# 307.net
KiCad netlist of a schematic drawn in EAGLE
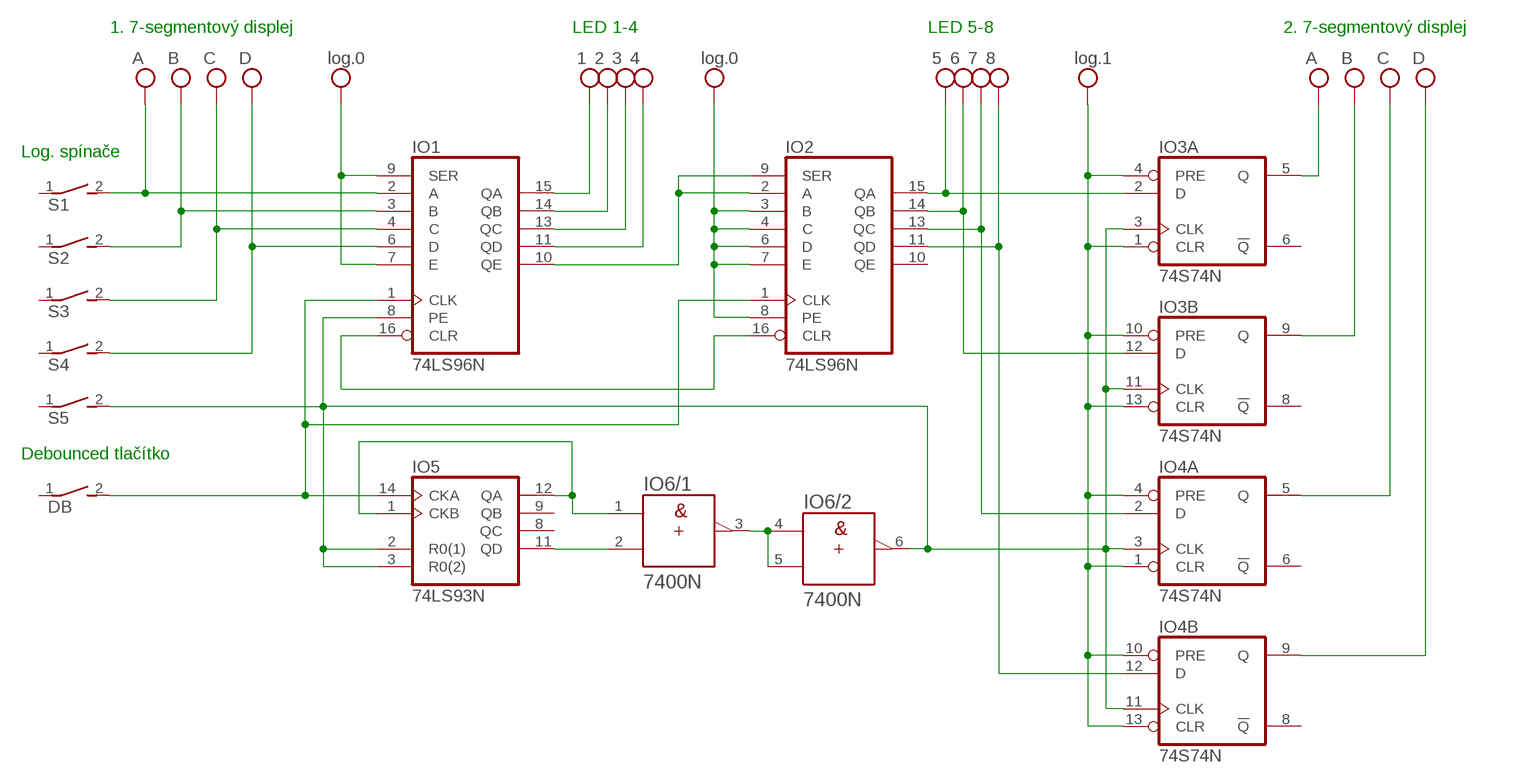
[diagram p0: schematic, sheet 1]

(export (version "E")
  (design (tool "Eeschema 10.0.6"))
  (components
    (comp (ref "DB")
      (value "DS01E")
      (footprint "eagle-import:DS-01")
      (libsource (lib "eagle-import") (part "DS01E"))
    )
    (comp (ref "IO1")
      (value "74LS96N")
      (footprint "eagle-import:DIL16")
      (libsource (lib "eagle-import") (part "7496NLS"))
    )
    (comp (ref "IO2")
      (value "74LS96N")
      (footprint "eagle-import:DIL16")
      (libsource (lib "eagle-import") (part "7496NLS"))
    )
    (comp (ref "IO3")
      (value "74S74N")
      (footprint "eagle-import:DIL14")
      (libsource (lib "eagle-import") (part "7474NS"))
    )
    (comp (ref "IO4")
      (value "74S74N")
      (footprint "eagle-import:DIL14")
      (libsource (lib "eagle-import") (part "7474NS"))
    )
    (comp (ref "IO5")
      (value "74LS93N")
      (footprint "eagle-import:DIL14")
      (libsource (lib "eagle-import") (part "7493NLS"))
    )
    (comp (ref "IO6")
      (value "7400N")
      (footprint "eagle-import:DIL14")
      (libsource (lib "eagle-import") (part "7400N"))
    )
    (comp (ref "S1")
      (value "DS01E")
      (footprint "eagle-import:DS-01")
      (libsource (lib "eagle-import") (part "DS01E"))
    )
    (comp (ref "S2")
      (value "DS01E")
      (footprint "eagle-import:DS-01")
      (libsource (lib "eagle-import") (part "DS01E"))
    )
    (comp (ref "S3")
      (value "DS01E")
      (footprint "eagle-import:DS-01")
      (libsource (lib "eagle-import") (part "DS01E"))
    )
    (comp (ref "S4")
      (value "DS01E")
      (footprint "eagle-import:DS-01")
      (libsource (lib "eagle-import") (part "DS01E"))
    )
    (comp (ref "S5")
      (value "DS01E")
      (footprint "eagle-import:DS-01")
      (libsource (lib "eagle-import") (part "DS01E"))
    )
  )
  (nets
    (net (code "1") (name "1") (class "Default")
      (node (ref "IO1") (pin "11") (pinfunction "QD_11") (pintype "output"))
      (node (ref "IO1") (pin "13") (pinfunction "QC_13") (pintype "output"))
      (node (ref "IO1") (pin "14") (pinfunction "QB_14") (pintype "output"))
      (node (ref "IO1") (pin "15") (pinfunction "QA_15") (pintype "output"))
      (node (ref "IO1") (pin "2") (pinfunction "A_2") (pintype "input"))
      (node (ref "IO1") (pin "3") (pinfunction "B_3") (pintype "input"))
      (node (ref "IO1") (pin "4") (pinfunction "C_4") (pintype "input"))
      (node (ref "IO1") (pin "6") (pinfunction "D_6") (pintype "input"))
      (node (ref "IO1") (pin "7") (pinfunction "E_7") (pintype "input"))
      (node (ref "IO1") (pin "9") (pinfunction "SER_9") (pintype "input"))
      (node (ref "IO2") (pin "11") (pinfunction "QD_11") (pintype "output"))
      (node (ref "IO2") (pin "13") (pinfunction "QC_13") (pintype "output"))
      (node (ref "IO2") (pin "14") (pinfunction "QB_14") (pintype "output"))
      (node (ref "IO2") (pin "15") (pinfunction "QA_15") (pintype "output"))
      (node (ref "IO2") (pin "3") (pinfunction "B_3") (pintype "input"))
      (node (ref "IO2") (pin "4") (pinfunction "C_4") (pintype "input"))
      (node (ref "IO2") (pin "6") (pinfunction "D_6") (pintype "input"))
      (node (ref "IO2") (pin "7") (pinfunction "E_7") (pintype "input"))
      (node (ref "IO2") (pin "8") (pinfunction "PE_8") (pintype "input"))
      (node (ref "IO3") (pin "1") (pinfunction "CLR_1") (pintype "input"))
      (node (ref "IO3") (pin "10") (pinfunction "PRE_10") (pintype "input"))
      (node (ref "IO3") (pin "12") (pinfunction "D_12") (pintype "input"))
      (node (ref "IO3") (pin "13") (pinfunction "CLR_13") (pintype "input"))
      (node (ref "IO3") (pin "2") (pinfunction "D_2") (pintype "input"))
      (node (ref "IO3") (pin "4") (pinfunction "PRE_4") (pintype "input"))
      (node (ref "IO3") (pin "5") (pinfunction "Q_5") (pintype "output"))
      (node (ref "IO3") (pin "9") (pinfunction "Q_9") (pintype "output"))
      (node (ref "IO4") (pin "1") (pinfunction "CLR_1") (pintype "input"))
      (node (ref "IO4") (pin "10") (pinfunction "PRE_10") (pintype "input"))
      (node (ref "IO4") (pin "12") (pinfunction "D_12") (pintype "input"))
      (node (ref "IO4") (pin "13") (pinfunction "CLR_13") (pintype "input"))
      (node (ref "IO4") (pin "2") (pinfunction "D_2") (pintype "input"))
      (node (ref "IO4") (pin "4") (pinfunction "PRE_4") (pintype "input"))
      (node (ref "IO4") (pin "5") (pinfunction "Q_5") (pintype "output"))
      (node (ref "IO4") (pin "9") (pinfunction "Q_9") (pintype "output"))
      (node (ref "S1") (pin "2") (pinfunction "2_2") (pintype "passive"))
      (node (ref "S2") (pin "2") (pinfunction "2_2") (pintype "passive"))
      (node (ref "S3") (pin "2") (pinfunction "2_2") (pintype "passive"))
      (node (ref "S4") (pin "2") (pinfunction "2_2") (pintype "passive"))
    )
    (net (code "2") (name "Net-(IO1A-CLK)") (class "Default")
      (node (ref "DB") (pin "2") (pinfunction "2_2") (pintype "passive"))
      (node (ref "IO1") (pin "1") (pinfunction "CLK_1") (pintype "input"))
      (node (ref "IO2") (pin "1") (pinfunction "CLK_1") (pintype "input"))
      (node (ref "IO5") (pin "14") (pinfunction "CKA_14") (pintype "input"))
    )
    (net (code "3") (name "Net-(IO1A-CLR)") (class "Default")
      (node (ref "IO1") (pin "16") (pinfunction "CLR_16") (pintype "input"))
      (node (ref "IO2") (pin "16") (pinfunction "CLR_16") (pintype "input"))
    )
    (net (code "4") (name "Net-(IO1A-PE)") (class "Default")
      (node (ref "IO1") (pin "8") (pinfunction "PE_8") (pintype "input"))
      (node (ref "IO3") (pin "11") (pinfunction "CLK_11") (pintype "input"))
      (node (ref "IO3") (pin "3") (pinfunction "CLK_3") (pintype "input"))
      (node (ref "IO4") (pin "11") (pinfunction "CLK_11") (pintype "input"))
      (node (ref "IO4") (pin "3") (pinfunction "CLK_3") (pintype "input"))
      (node (ref "IO5") (pin "2") (pinfunction "R0(1)_2") (pintype "input"))
      (node (ref "IO5") (pin "3") (pinfunction "R0(2)_3") (pintype "input"))
      (node (ref "IO6") (pin "6") (pinfunction "Y_6") (pintype "output"))
      (node (ref "S5") (pin "2") (pinfunction "2_2") (pintype "passive"))
    )
    (net (code "5") (name "Net-(IO1A-QE)") (class "Default")
      (node (ref "IO1") (pin "10") (pinfunction "QE_10") (pintype "output"))
      (node (ref "IO2") (pin "2") (pinfunction "A_2") (pintype "input"))
      (node (ref "IO2") (pin "9") (pinfunction "SER_9") (pintype "input"))
    )
    (net (code "6") (name "Net-(IO5A-CKB)") (class "Default")
      (node (ref "IO5") (pin "1") (pinfunction "CKB_1") (pintype "input"))
      (node (ref "IO5") (pin "12") (pinfunction "QA_12") (pintype "output"))
      (node (ref "IO6") (pin "1") (pinfunction "A_1") (pintype "input"))
    )
    (net (code "7") (name "Net-(IO5A-QD)") (class "Default")
      (node (ref "IO5") (pin "11") (pinfunction "QD_11") (pintype "output"))
      (node (ref "IO6") (pin "2") (pinfunction "B_2") (pintype "input"))
    )
    (net (code "8") (name "Net-(IO6C-Y)") (class "Default")
      (node (ref "IO6") (pin "3") (pinfunction "Y_3") (pintype "output"))
      (node (ref "IO6") (pin "4") (pinfunction "A_4") (pintype "input"))
      (node (ref "IO6") (pin "5") (pinfunction "B_5") (pintype "input"))
    )
    (net (code "9") (name "unconnected-(DB-Pad1)") (class "Default")
      (node (ref "DB") (pin "1") (pinfunction "1_1") (pintype "passive"))
    )
    (net (code "10") (name "unconnected-(IO2A-QE-Pad10)") (class "Default")
      (node (ref "IO2") (pin "10") (pinfunction "QE_10") (pintype "output"))
    )
    (net (code "11") (name "unconnected-(IO3A-~{Q}-Pad6)") (class "Default")
      (node (ref "IO3") (pin "6") (pinfunction "~{Q}_6") (pintype "output"))
    )
    (net (code "12") (name "unconnected-(IO3B-~{Q}-Pad8)") (class "Default")
      (node (ref "IO3") (pin "8") (pinfunction "~{Q}_8") (pintype "output"))
    )
    (net (code "13") (name "unconnected-(IO4A-~{Q}-Pad6)") (class "Default")
      (node (ref "IO4") (pin "6") (pinfunction "~{Q}_6") (pintype "output"))
    )
    (net (code "14") (name "unconnected-(IO4B-~{Q}-Pad8)") (class "Default")
      (node (ref "IO4") (pin "8") (pinfunction "~{Q}_8") (pintype "output"))
    )
    (net (code "15") (name "unconnected-(IO5A-QB-Pad9)") (class "Default")
      (node (ref "IO5") (pin "9") (pinfunction "QB_9") (pintype "output"))
    )
    (net (code "16") (name "unconnected-(IO5A-QC-Pad8)") (class "Default")
      (node (ref "IO5") (pin "8") (pinfunction "QC_8") (pintype "output"))
    )
    (net (code "17") (name "unconnected-(S1-Pad1)") (class "Default")
      (node (ref "S1") (pin "1") (pinfunction "1_1") (pintype "passive"))
    )
    (net (code "18") (name "unconnected-(S2-Pad1)") (class "Default")
      (node (ref "S2") (pin "1") (pinfunction "1_1") (pintype "passive"))
    )
    (net (code "19") (name "unconnected-(S3-Pad1)") (class "Default")
      (node (ref "S3") (pin "1") (pinfunction "1_1") (pintype "passive"))
    )
    (net (code "20") (name "unconnected-(S4-Pad1)") (class "Default")
      (node (ref "S4") (pin "1") (pinfunction "1_1") (pintype "passive"))
    )
    (net (code "21") (name "unconnected-(S5-Pad1)") (class "Default")
      (node (ref "S5") (pin "1") (pinfunction "1_1") (pintype "passive"))
    )
  )
)
